# M452XX.net
KiCad netlist of a schematic drawn in EAGLE
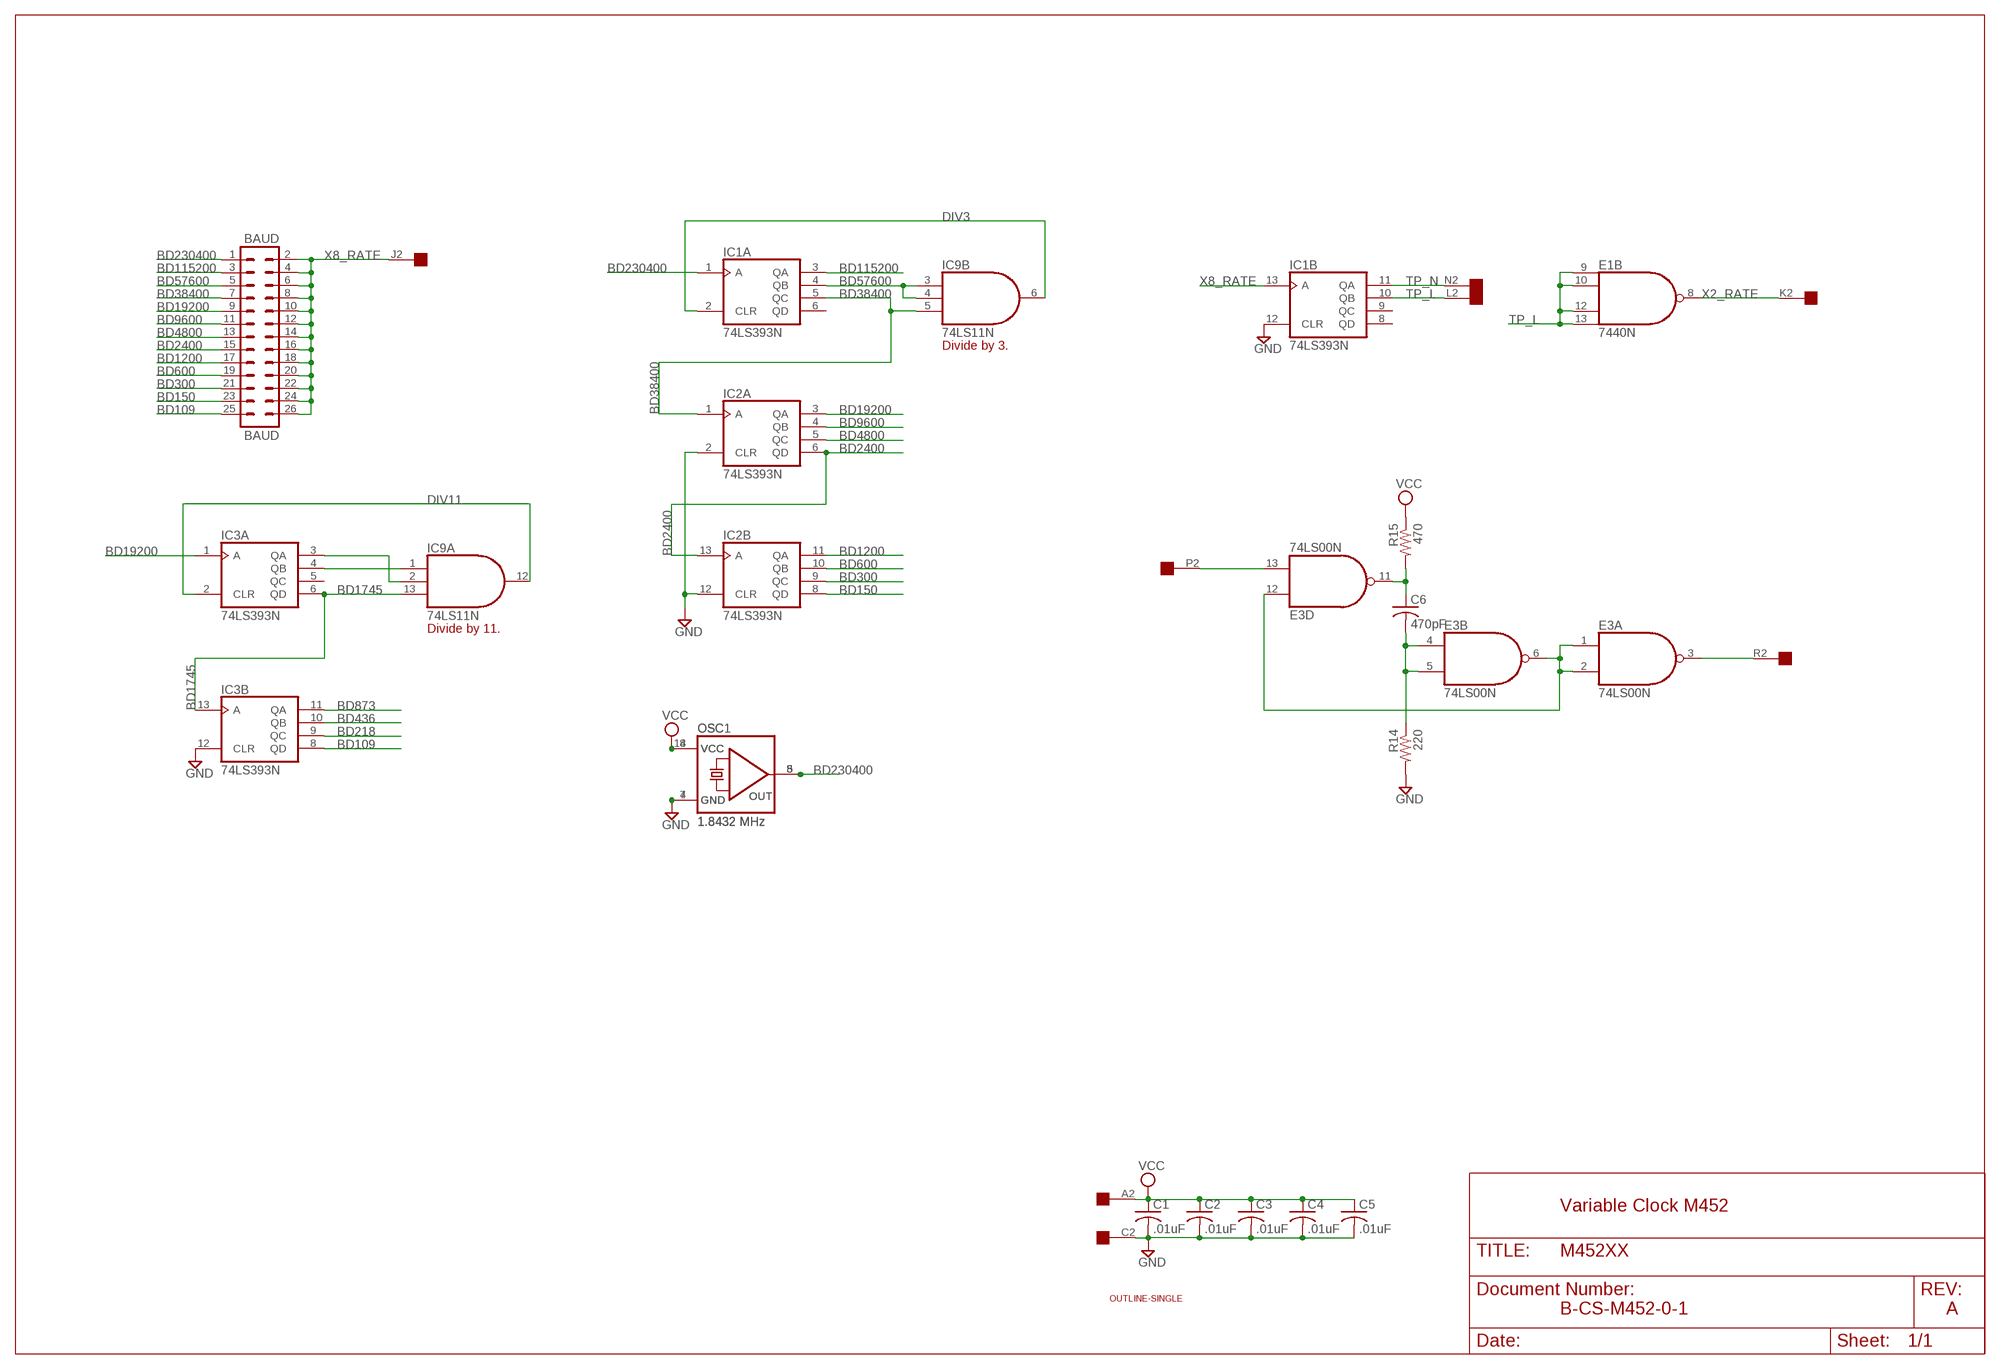
[diagram p0: schematic, sheet 1]

(export (version "E")
  (design (tool "Eeschema 10.0.6"))
  (components
    (comp (ref "BAUD")
      (value "BAUD")
      (footprint "eagle-import:MA13-2")
      (libsource (lib "eagle-import") (part "MA13-2"))
    )
    (comp (ref "C1")
      (value ".01uF")
      (footprint "eagle-import:C050-025X075")
      (libsource (lib "eagle-import") (part "C-US050-025X075"))
    )
    (comp (ref "C2")
      (value ".01uF")
      (footprint "eagle-import:C050-025X075")
      (libsource (lib "eagle-import") (part "C-US050-025X075"))
    )
    (comp (ref "C3")
      (value ".01uF")
      (footprint "eagle-import:C050-025X075")
      (libsource (lib "eagle-import") (part "C-US050-025X075"))
    )
    (comp (ref "C4")
      (value ".01uF")
      (footprint "eagle-import:C050-025X075")
      (libsource (lib "eagle-import") (part "C-US050-025X075"))
    )
    (comp (ref "C5")
      (value ".01uF")
      (footprint "eagle-import:C050-025X075")
      (libsource (lib "eagle-import") (part "C-US050-025X075"))
    )
    (comp (ref "C6")
      (value "470pF")
      (footprint "eagle-import:C150-054X183")
      (libsource (lib "eagle-import") (part "C-US150-054X183"))
    )
    (comp (ref "E1")
      (value "7440N")
      (footprint "eagle-import:DIL14")
      (libsource (lib "eagle-import") (part "7420NS"))
    )
    (comp (ref "E3")
      (value "74LS00N")
      (footprint "eagle-import:DIL14")
      (libsource (lib "eagle-import") (part "7400NLS"))
    )
    (comp (ref "IC1")
      (value "74LS393N")
      (footprint "eagle-import:DIL14")
      (libsource (lib "eagle-import") (part "74393NLS"))
    )
    (comp (ref "IC2")
      (value "74LS393N")
      (footprint "eagle-import:DIL14")
      (libsource (lib "eagle-import") (part "74393NLS"))
    )
    (comp (ref "IC3")
      (value "74LS393N")
      (footprint "eagle-import:DIL14")
      (libsource (lib "eagle-import") (part "74393NLS"))
    )
    (comp (ref "IC9")
      (value "74LS11N")
      (footprint "eagle-import:DIL14")
      (libsource (lib "eagle-import") (part "7411NLS"))
    )
    (comp (ref "OSC")
      (value "1.8432 MHz")
      (footprint "eagle-import:DIL08S")
      (libsource (lib "eagle-import") (part "QG5460"))
    )
    (comp (ref "OSC1")
      (value "1.8432 MHz")
      (footprint "eagle-import:DIL14S")
      (libsource (lib "eagle-import") (part "QG5860"))
    )
    (comp (ref "R14")
      (value "220")
      (footprint "eagle-import:0207_10")
      (libsource (lib "eagle-import") (part "R-US_0207/10"))
    )
    (comp (ref "R15")
      (value "470")
      (footprint "eagle-import:0207_10")
      (libsource (lib "eagle-import") (part "R-US_0207/10"))
    )
    (comp (ref "U$1")
      (value "OUTLINE-SINGLE")
      (footprint "eagle-import:SINGLE")
      (libsource (lib "eagle-import") (part "OUTLINE-SINGLE"))
    )
    (comp (ref "U$2")
      (value "EDGE-1")
      (footprint "eagle-import:EDGE-CON1")
      (libsource (lib "eagle-import") (part "EDGE-1"))
    )
  )
  (nets
    (net (code "1") (name "/BD109") (class "Default")
      (node (ref "BAUD") (pin "25") (pinfunction "25_25") (pintype "passive"))
      (node (ref "IC3") (pin "8") (pinfunction "QD_8") (pintype "output"))
    )
    (net (code "2") (name "/BD150") (class "Default")
      (node (ref "BAUD") (pin "23") (pinfunction "23_23") (pintype "passive"))
      (node (ref "IC2") (pin "8") (pinfunction "QD_8") (pintype "output"))
    )
    (net (code "3") (name "/BD218") (class "Default")
      (node (ref "IC3") (pin "9") (pinfunction "QC_9") (pintype "output"))
    )
    (net (code "4") (name "/BD300") (class "Default")
      (node (ref "BAUD") (pin "21") (pinfunction "21_21") (pintype "passive"))
      (node (ref "IC2") (pin "9") (pinfunction "QC_9") (pintype "output"))
    )
    (net (code "5") (name "/BD436") (class "Default")
      (node (ref "IC3") (pin "10") (pinfunction "QB_10") (pintype "output"))
    )
    (net (code "6") (name "/BD600") (class "Default")
      (node (ref "BAUD") (pin "19") (pinfunction "19_19") (pintype "passive"))
      (node (ref "IC2") (pin "10") (pinfunction "QB_10") (pintype "output"))
    )
    (net (code "7") (name "/BD873") (class "Default")
      (node (ref "IC3") (pin "11") (pinfunction "QA_11") (pintype "output"))
    )
    (net (code "8") (name "/BD1200") (class "Default")
      (node (ref "BAUD") (pin "17") (pinfunction "17_17") (pintype "passive"))
      (node (ref "IC2") (pin "11") (pinfunction "QA_11") (pintype "output"))
    )
    (net (code "9") (name "/BD1745") (class "Default")
      (node (ref "IC3") (pin "13") (pinfunction "A_13") (pintype "input"))
      (node (ref "IC3") (pin "6") (pinfunction "QD_6") (pintype "output"))
      (node (ref "IC9") (pin "13") (pinfunction "I2_13") (pintype "input"))
    )
    (net (code "10") (name "/BD2400") (class "Default")
      (node (ref "BAUD") (pin "15") (pinfunction "15_15") (pintype "passive"))
      (node (ref "IC2") (pin "13") (pinfunction "A_13") (pintype "input"))
      (node (ref "IC2") (pin "6") (pinfunction "QD_6") (pintype "output"))
    )
    (net (code "11") (name "/BD4800") (class "Default")
      (node (ref "BAUD") (pin "13") (pinfunction "13_13") (pintype "passive"))
      (node (ref "IC2") (pin "5") (pinfunction "QC_5") (pintype "output"))
    )
    (net (code "12") (name "/BD9600") (class "Default")
      (node (ref "BAUD") (pin "11") (pinfunction "11_11") (pintype "passive"))
      (node (ref "IC2") (pin "4") (pinfunction "QB_4") (pintype "output"))
    )
    (net (code "13") (name "/BD19200") (class "Default")
      (node (ref "BAUD") (pin "9") (pinfunction "9_9") (pintype "passive"))
      (node (ref "IC2") (pin "3") (pinfunction "QA_3") (pintype "output"))
      (node (ref "IC3") (pin "1") (pinfunction "A_1") (pintype "input"))
    )
    (net (code "14") (name "/BD38400") (class "Default")
      (node (ref "BAUD") (pin "7") (pinfunction "7_7") (pintype "passive"))
      (node (ref "IC1") (pin "5") (pinfunction "QC_5") (pintype "output"))
      (node (ref "IC2") (pin "1") (pinfunction "A_1") (pintype "input"))
      (node (ref "IC9") (pin "5") (pinfunction "I2_5") (pintype "input"))
    )
    (net (code "15") (name "/BD57600") (class "Default")
      (node (ref "BAUD") (pin "5") (pinfunction "5_5") (pintype "passive"))
      (node (ref "IC1") (pin "4") (pinfunction "QB_4") (pintype "output"))
      (node (ref "IC9") (pin "3") (pinfunction "I0_3") (pintype "input"))
      (node (ref "IC9") (pin "4") (pinfunction "I1_4") (pintype "input"))
    )
    (net (code "16") (name "/BD115200") (class "Default")
      (node (ref "BAUD") (pin "3") (pinfunction "3_3") (pintype "passive"))
      (node (ref "IC1") (pin "3") (pinfunction "QA_3") (pintype "output"))
    )
    (net (code "17") (name "/BD230400") (class "Default")
      (node (ref "BAUD") (pin "1") (pinfunction "1_1") (pintype "passive"))
      (node (ref "IC1") (pin "1") (pinfunction "A_1") (pintype "input"))
      (node (ref "OSC") (pin "5") (pinfunction "OUT_5") (pintype "output"))
      (node (ref "OSC1") (pin "8") (pinfunction "OUT_8") (pintype "output"))
    )
    (net (code "18") (name "/DIV3") (class "Default")
      (node (ref "IC1") (pin "2") (pinfunction "CLR_2") (pintype "input"))
      (node (ref "IC9") (pin "6") (pinfunction "O_6") (pintype "output"))
    )
    (net (code "19") (name "/DIV11") (class "Default")
      (node (ref "IC3") (pin "2") (pinfunction "CLR_2") (pintype "input"))
      (node (ref "IC9") (pin "12") (pinfunction "O_12") (pintype "output"))
    )
    (net (code "20") (name "/TP_L") (class "Default")
      (node (ref "E1") (pin "10") (pinfunction "I1_10") (pintype "input"))
      (node (ref "E1") (pin "12") (pinfunction "I2_12") (pintype "input"))
      (node (ref "E1") (pin "13") (pinfunction "I3_13") (pintype "input"))
      (node (ref "E1") (pin "9") (pinfunction "I0_9") (pintype "input"))
      (node (ref "IC1") (pin "10") (pinfunction "QB_10") (pintype "output"))
      (node (ref "U$2") (pin "L2") (pinfunction "1_L2") (pintype "bidirectional"))
    )
    (net (code "21") (name "/TP_N") (class "Default")
      (node (ref "IC1") (pin "11") (pinfunction "QA_11") (pintype "output"))
      (node (ref "U$2") (pin "N2") (pinfunction "1_N2") (pintype "bidirectional"))
    )
    (net (code "22") (name "/X2_RATE") (class "Default")
      (node (ref "E1") (pin "8") (pinfunction "O_8") (pintype "output"))
      (node (ref "U$2") (pin "K2") (pinfunction "1_K2") (pintype "bidirectional"))
    )
    (net (code "23") (name "/X8_RATE") (class "Default")
      (node (ref "BAUD") (pin "10") (pinfunction "10_10") (pintype "passive"))
      (node (ref "BAUD") (pin "12") (pinfunction "12_12") (pintype "passive"))
      (node (ref "BAUD") (pin "14") (pinfunction "14_14") (pintype "passive"))
      (node (ref "BAUD") (pin "16") (pinfunction "16_16") (pintype "passive"))
      (node (ref "BAUD") (pin "18") (pinfunction "18_18") (pintype "passive"))
      (node (ref "BAUD") (pin "2") (pinfunction "2_2") (pintype "passive"))
      (node (ref "BAUD") (pin "20") (pinfunction "20_20") (pintype "passive"))
      (node (ref "BAUD") (pin "22") (pinfunction "22_22") (pintype "passive"))
      (node (ref "BAUD") (pin "24") (pinfunction "24_24") (pintype "passive"))
      (node (ref "BAUD") (pin "26") (pinfunction "26_26") (pintype "passive"))
      (node (ref "BAUD") (pin "4") (pinfunction "4_4") (pintype "passive"))
      (node (ref "BAUD") (pin "6") (pinfunction "6_6") (pintype "passive"))
      (node (ref "BAUD") (pin "8") (pinfunction "8_8") (pintype "passive"))
      (node (ref "IC1") (pin "13") (pinfunction "A_13") (pintype "input"))
      (node (ref "U$2") (pin "J2") (pinfunction "1_J2") (pintype "bidirectional"))
    )
    (net (code "24") (name "GND") (class "Default")
      (node (ref "C1") (pin "2") (pinfunction "2_2") (pintype "passive"))
      (node (ref "C2") (pin "2") (pinfunction "2_2") (pintype "passive"))
      (node (ref "C3") (pin "2") (pinfunction "2_2") (pintype "passive"))
      (node (ref "C4") (pin "2") (pinfunction "2_2") (pintype "passive"))
      (node (ref "C5") (pin "2") (pinfunction "2_2") (pintype "passive"))
      (node (ref "IC1") (pin "12") (pinfunction "CLR_12") (pintype "input"))
      (node (ref "IC2") (pin "12") (pinfunction "CLR_12") (pintype "input"))
      (node (ref "IC2") (pin "2") (pinfunction "CLR_2") (pintype "input"))
      (node (ref "IC3") (pin "12") (pinfunction "CLR_12") (pintype "input"))
      (node (ref "OSC") (pin "4") (pinfunction "GND_4") (pintype "power_in"))
      (node (ref "OSC1") (pin "7") (pinfunction "GND_7") (pintype "power_in"))
      (node (ref "R14") (pin "2") (pinfunction "2_2") (pintype "passive"))
      (node (ref "U$2") (pin "C2") (pinfunction "1_C2") (pintype "bidirectional"))
    )
    (net (code "25") (name "Net-(E3A-I0)") (class "Default")
      (node (ref "E3") (pin "1") (pinfunction "I0_1") (pintype "input"))
      (node (ref "E3") (pin "12") (pinfunction "I0_12") (pintype "input"))
      (node (ref "E3") (pin "2") (pinfunction "I1_2") (pintype "input"))
      (node (ref "E3") (pin "6") (pinfunction "O_6") (pintype "output"))
    )
    (net (code "26") (name "Net-(E3A-O)") (class "Default")
      (node (ref "E3") (pin "3") (pinfunction "O_3") (pintype "output"))
      (node (ref "U$2") (pin "R2") (pinfunction "1_R2") (pintype "bidirectional"))
    )
    (net (code "27") (name "Net-(E3B-I0)") (class "Default")
      (node (ref "C6") (pin "2") (pinfunction "2_2") (pintype "passive"))
      (node (ref "E3") (pin "4") (pinfunction "I0_4") (pintype "input"))
      (node (ref "E3") (pin "5") (pinfunction "I1_5") (pintype "input"))
      (node (ref "R14") (pin "1") (pinfunction "1_1") (pintype "passive"))
    )
    (net (code "28") (name "Net-(E3D-I1)") (class "Default")
      (node (ref "E3") (pin "13") (pinfunction "I1_13") (pintype "input"))
      (node (ref "U$2") (pin "P2") (pinfunction "1_P2") (pintype "bidirectional"))
    )
    (net (code "29") (name "Net-(E3D-O)") (class "Default")
      (node (ref "C6") (pin "1") (pinfunction "1_1") (pintype "passive"))
      (node (ref "E3") (pin "11") (pinfunction "O_11") (pintype "output"))
      (node (ref "R15") (pin "2") (pinfunction "2_2") (pintype "passive"))
    )
    (net (code "30") (name "Net-(IC3A-QA)") (class "Default")
      (node (ref "IC3") (pin "3") (pinfunction "QA_3") (pintype "output"))
      (node (ref "IC9") (pin "2") (pinfunction "I1_2") (pintype "input"))
    )
    (net (code "31") (name "Net-(IC3A-QB)") (class "Default")
      (node (ref "IC3") (pin "4") (pinfunction "QB_4") (pintype "output"))
      (node (ref "IC9") (pin "1") (pinfunction "I0_1") (pintype "input"))
    )
    (net (code "32") (name "VCC") (class "Default")
      (node (ref "C1") (pin "1") (pinfunction "1_1") (pintype "passive"))
      (node (ref "C2") (pin "1") (pinfunction "1_1") (pintype "passive"))
      (node (ref "C3") (pin "1") (pinfunction "1_1") (pintype "passive"))
      (node (ref "C4") (pin "1") (pinfunction "1_1") (pintype "passive"))
      (node (ref "C5") (pin "1") (pinfunction "1_1") (pintype "passive"))
      (node (ref "OSC") (pin "8") (pinfunction "VCC_8") (pintype "power_in"))
      (node (ref "OSC1") (pin "14") (pinfunction "VCC_14") (pintype "power_in"))
      (node (ref "R15") (pin "1") (pinfunction "1_1") (pintype "passive"))
      (node (ref "U$2") (pin "A2") (pinfunction "1_A2") (pintype "bidirectional"))
    )
    (net (code "33") (name "unconnected-(IC1A-QD-Pad6)") (class "Default")
      (node (ref "IC1") (pin "6") (pinfunction "QD_6") (pintype "output"))
    )
    (net (code "34") (name "unconnected-(IC1B-QC-Pad9)") (class "Default")
      (node (ref "IC1") (pin "9") (pinfunction "QC_9") (pintype "output"))
    )
    (net (code "35") (name "unconnected-(IC1B-QD-Pad8)") (class "Default")
      (node (ref "IC1") (pin "8") (pinfunction "QD_8") (pintype "output"))
    )
    (net (code "36") (name "unconnected-(IC3A-QC-Pad5)") (class "Default")
      (node (ref "IC3") (pin "5") (pinfunction "QC_5") (pintype "output"))
    )
  )
)
